# board.net
KiCad netlist of a schematic drawn in EAGLE
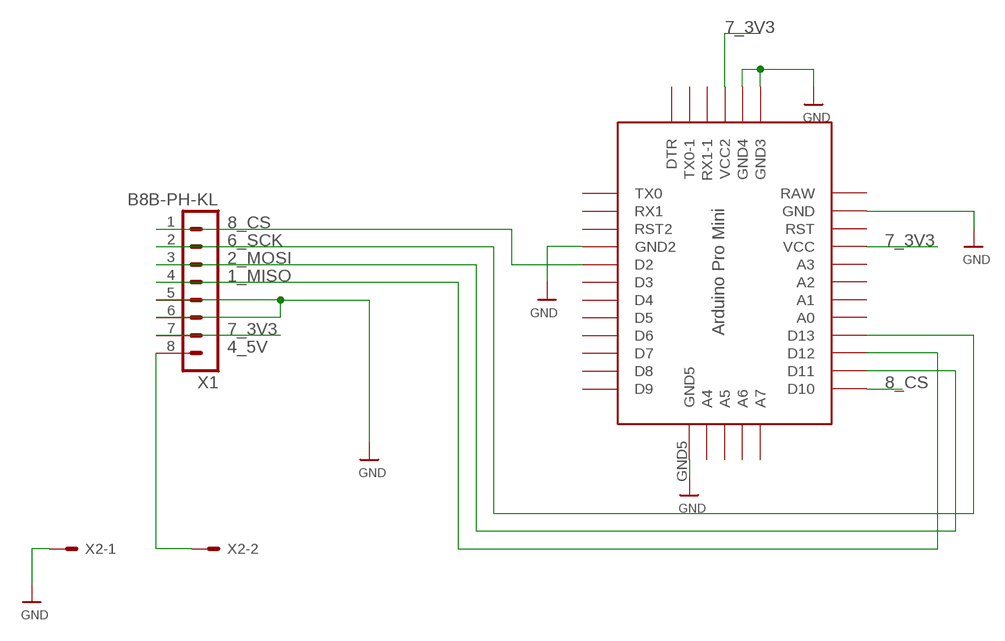
[diagram p0: schematic, sheet 1]

(export (version "E")
  (design (tool "Eeschema 10.0.6"))
  (components
    (comp (ref "U$7")
      (value "PRO-MINI_5BOT")
      (footprint "eagle-import:PRO-MINI-5BOT")
      (libsource (lib "eagle-import") (part "PRO-MINI_5BOT"))
    )
    (comp (ref "X1")
      (value "B8B-PH-KL")
      (footprint "eagle-import:B8B-PH-K-S")
      (libsource (lib "eagle-import") (part "B8B-PH-KL"))
    )
    (comp (ref "X2")
      (value "87758-0216")
      (footprint "eagle-import:87758-0216")
      (fields (field (name "MF") "MOLEX"))
      (libsource (lib "eagle-import") (part "87758-0216"))
    )
  )
  (nets
    (net (code "1") (name "/1_MISO") (class "Default")
      (node (ref "U$7") (pin "D12") (pinfunction "D12_D12") (pintype "bidirectional"))
      (node (ref "X1") (pin "4") (pinfunction "4_4") (pintype "passive"))
    )
    (net (code "2") (name "/2_MOSI") (class "Default")
      (node (ref "U$7") (pin "D11") (pinfunction "D11_D11") (pintype "bidirectional"))
      (node (ref "X1") (pin "3") (pinfunction "3_3") (pintype "passive"))
    )
    (net (code "3") (name "/4_5V") (class "Default")
      (node (ref "X1") (pin "8") (pinfunction "8_8") (pintype "passive"))
      (node (ref "X2") (pin "2") (pinfunction "S_2") (pintype "passive"))
    )
    (net (code "4") (name "/6_SCK") (class "Default")
      (node (ref "U$7") (pin "D13") (pinfunction "D13_D13") (pintype "bidirectional"))
      (node (ref "X1") (pin "2") (pinfunction "2_2") (pintype "passive"))
    )
    (net (code "5") (name "/7_3V3") (class "Default")
      (node (ref "U$7") (pin "VCC") (pinfunction "VCC_VCC") (pintype "bidirectional"))
      (node (ref "U$7") (pin "VCC2") (pinfunction "VCC2_VCC2") (pintype "bidirectional"))
      (node (ref "X1") (pin "7") (pinfunction "7_7") (pintype "passive"))
    )
    (net (code "6") (name "/8_CS") (class "Default")
      (node (ref "U$7") (pin "D10") (pinfunction "D10_D10") (pintype "bidirectional"))
      (node (ref "U$7") (pin "D2") (pinfunction "D2_D2") (pintype "bidirectional"))
      (node (ref "X1") (pin "1") (pinfunction "1_1") (pintype "passive"))
    )
    (net (code "7") (name "/RAW") (class "Default")
      (node (ref "U$7") (pin "RAW") (pinfunction "RAW_RAW") (pintype "power_in"))
    )
    (net (code "8") (name "GND") (class "Default")
      (node (ref "U$7") (pin "GND") (pinfunction "GND_GND") (pintype "input"))
      (node (ref "U$7") (pin "GND2") (pinfunction "GND2_GND2") (pintype "bidirectional"))
      (node (ref "U$7") (pin "GND3") (pinfunction "GND3_GND3") (pintype "bidirectional"))
      (node (ref "U$7") (pin "GND4") (pinfunction "GND4_GND4") (pintype "bidirectional"))
      (node (ref "U$7") (pin "GND5") (pinfunction "GND5_GND5") (pintype "bidirectional"))
      (node (ref "X1") (pin "5") (pinfunction "5_5") (pintype "passive"))
      (node (ref "X1") (pin "6") (pinfunction "6_6") (pintype "passive"))
      (node (ref "X2") (pin "1") (pinfunction "S_1") (pintype "passive"))
    )
    (net (code "9") (name "unconnected-(U$7-PadA0)") (class "Default")
      (node (ref "U$7") (pin "A0") (pinfunction "A0_A0") (pintype "bidirectional"))
    )
    (net (code "10") (name "unconnected-(U$7-PadA1)") (class "Default")
      (node (ref "U$7") (pin "A1") (pinfunction "A1_A1") (pintype "bidirectional"))
    )
    (net (code "11") (name "unconnected-(U$7-PadA2)") (class "Default")
      (node (ref "U$7") (pin "A2") (pinfunction "A2_A2") (pintype "bidirectional"))
    )
    (net (code "12") (name "unconnected-(U$7-PadA3)") (class "Default")
      (node (ref "U$7") (pin "A3") (pinfunction "A3_A3") (pintype "bidirectional"))
    )
    (net (code "13") (name "unconnected-(U$7-PadA4)") (class "Default")
      (node (ref "U$7") (pin "A4") (pinfunction "A4_A4") (pintype "bidirectional"))
    )
    (net (code "14") (name "unconnected-(U$7-PadA5)") (class "Default")
      (node (ref "U$7") (pin "A5") (pinfunction "A5_A5") (pintype "bidirectional"))
    )
    (net (code "15") (name "unconnected-(U$7-PadA6)") (class "Default")
      (node (ref "U$7") (pin "A6") (pinfunction "A6_A6") (pintype "bidirectional"))
    )
    (net (code "16") (name "unconnected-(U$7-PadA7)") (class "Default")
      (node (ref "U$7") (pin "A7") (pinfunction "A7_A7") (pintype "bidirectional"))
    )
    (net (code "17") (name "unconnected-(U$7-PadD3)") (class "Default")
      (node (ref "U$7") (pin "D3") (pinfunction "D3_D3") (pintype "bidirectional"))
    )
    (net (code "18") (name "unconnected-(U$7-PadD4)") (class "Default")
      (node (ref "U$7") (pin "D4") (pinfunction "D4_D4") (pintype "bidirectional"))
    )
    (net (code "19") (name "unconnected-(U$7-PadD5)") (class "Default")
      (node (ref "U$7") (pin "D5") (pinfunction "D5_D5") (pintype "bidirectional"))
    )
    (net (code "20") (name "unconnected-(U$7-PadD6)") (class "Default")
      (node (ref "U$7") (pin "D6") (pinfunction "D6_D6") (pintype "bidirectional"))
    )
    (net (code "21") (name "unconnected-(U$7-PadD7)") (class "Default")
      (node (ref "U$7") (pin "D7") (pinfunction "D7_D7") (pintype "bidirectional"))
    )
    (net (code "22") (name "unconnected-(U$7-PadD8)") (class "Default")
      (node (ref "U$7") (pin "D8") (pinfunction "D8_D8") (pintype "bidirectional"))
    )
    (net (code "23") (name "unconnected-(U$7-PadD9)") (class "Default")
      (node (ref "U$7") (pin "D9") (pinfunction "D9_D9") (pintype "bidirectional"))
    )
    (net (code "24") (name "unconnected-(U$7-PadDTR)") (class "Default")
      (node (ref "U$7") (pin "DTR") (pinfunction "DTR_DTR") (pintype "bidirectional"))
    )
    (net (code "25") (name "unconnected-(U$7-PadRST)") (class "Default")
      (node (ref "U$7") (pin "RST") (pinfunction "RST_RST") (pintype "bidirectional"))
    )
    (net (code "26") (name "unconnected-(U$7-PadRST2)") (class "Default")
      (node (ref "U$7") (pin "RST2") (pinfunction "RST2_RST2") (pintype "bidirectional"))
    )
    (net (code "27") (name "unconnected-(U$7-PadRX1)") (class "Default")
      (node (ref "U$7") (pin "RX1") (pinfunction "RX1_RX1") (pintype "bidirectional"))
    )
    (net (code "28") (name "unconnected-(U$7-PadRX1-1)") (class "Default")
      (node (ref "U$7") (pin "RX1-1") (pinfunction "RX1-1_RX1-1") (pintype "bidirectional"))
    )
    (net (code "29") (name "unconnected-(U$7-PadTX0)") (class "Default")
      (node (ref "U$7") (pin "TX0") (pinfunction "TX0_TX0") (pintype "bidirectional"))
    )
    (net (code "30") (name "unconnected-(U$7-PadTX0-1)") (class "Default")
      (node (ref "U$7") (pin "TX0-1") (pinfunction "TX0-1_TX0-1") (pintype "bidirectional"))
    )
  )
)
